# Motors_and_Steering.net
KiCad netlist of a schematic drawn in Altium Designer
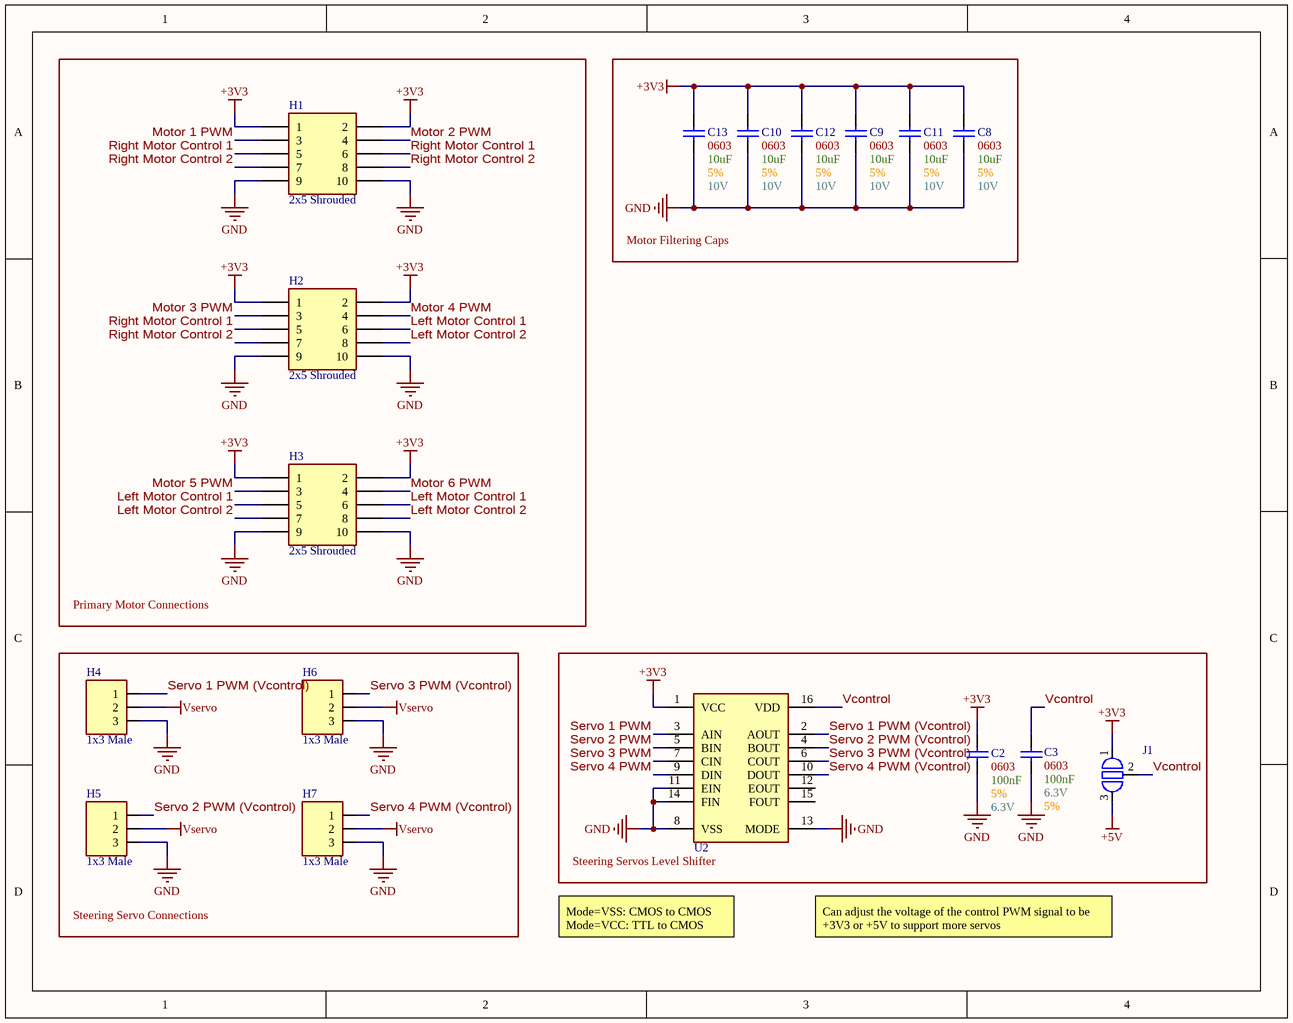
[diagram p0: Motors and Steering.SchDoc]

(export (version "E")
  (design (tool "Eeschema 10.0.6"))
  (components
    (comp (ref "C2")
      (value "[Cap] SMD Nonpolarized")
      (footprint "[Cap] SMD 0603")
      (fields
        (field (name "SIZE PACKAGE") "0603")
        (field (name "CAPACITANCE") "100nF")
        (field (name "VOLTAGE") "6.3V")
        (field (name "TOLERANCE") "5%")
      )
      (libsource (lib "RADM Components") (part "[Cap] SMD Nonpolarized"))
    )
    (comp (ref "C3")
      (value "[Cap] SMD Nonpolarized")
      (footprint "[Cap] SMD 0603")
      (fields
        (field (name "SIZE PACKAGE") "0603")
        (field (name "CAPACITANCE") "100nF")
        (field (name "VOLTAGE") "6.3V")
        (field (name "TOLERANCE") "5%")
      )
      (libsource (lib "RADM Components") (part "[Cap] SMD Nonpolarized"))
    )
    (comp (ref "C8")
      (value "[Cap] SMD Nonpolarized")
      (footprint "[Cap] SMD 0603")
      (fields
        (field (name "SIZE PACKAGE") "0603")
        (field (name "CAPACITANCE") "10uF")
        (field (name "VOLTAGE") "10V")
        (field (name "TOLERANCE") "5%")
      )
      (libsource (lib "RADM Components") (part "[Cap] SMD Nonpolarized"))
    )
    (comp (ref "C9")
      (value "[Cap] SMD Nonpolarized")
      (footprint "[Cap] SMD 0603")
      (fields
        (field (name "SIZE PACKAGE") "0603")
        (field (name "CAPACITANCE") "10uF")
        (field (name "VOLTAGE") "10V")
        (field (name "TOLERANCE") "5%")
      )
      (libsource (lib "RADM Components") (part "[Cap] SMD Nonpolarized"))
    )
    (comp (ref "C10")
      (value "[Cap] SMD Nonpolarized")
      (footprint "[Cap] SMD 0603")
      (fields
        (field (name "SIZE PACKAGE") "0603")
        (field (name "CAPACITANCE") "10uF")
        (field (name "VOLTAGE") "10V")
        (field (name "TOLERANCE") "5%")
      )
      (libsource (lib "RADM Components") (part "[Cap] SMD Nonpolarized"))
    )
    (comp (ref "C11")
      (value "[Cap] SMD Nonpolarized")
      (footprint "[Cap] SMD 0603")
      (fields
        (field (name "SIZE PACKAGE") "0603")
        (field (name "CAPACITANCE") "10uF")
        (field (name "VOLTAGE") "10V")
        (field (name "TOLERANCE") "5%")
      )
      (libsource (lib "RADM Components") (part "[Cap] SMD Nonpolarized"))
    )
    (comp (ref "C12")
      (value "[Cap] SMD Nonpolarized")
      (footprint "[Cap] SMD 0603")
      (fields
        (field (name "SIZE PACKAGE") "0603")
        (field (name "CAPACITANCE") "10uF")
        (field (name "VOLTAGE") "10V")
        (field (name "TOLERANCE") "5%")
      )
      (libsource (lib "RADM Components") (part "[Cap] SMD Nonpolarized"))
    )
    (comp (ref "C13")
      (value "[Cap] SMD Nonpolarized")
      (footprint "[Cap] SMD 0603")
      (fields
        (field (name "SIZE PACKAGE") "0603")
        (field (name "CAPACITANCE") "10uF")
        (field (name "VOLTAGE") "10V")
        (field (name "TOLERANCE") "5%")
      )
      (libsource (lib "RADM Components") (part "[Cap] SMD Nonpolarized"))
    )
    (comp (ref "H1")
      (value "2x5 Shrouded")
      (footprint "[Header] Shrouded 2x5 Male")
      (description "BHR-10-VUA")
      (libsource (lib "RADM Connectors") (part "[Header] Shrouded 2x5 Male"))
    )
    (comp (ref "H2")
      (value "2x5 Shrouded")
      (footprint "[Header] Shrouded 2x5 Male")
      (description "BHR-10-VUA")
      (libsource (lib "RADM Connectors") (part "[Header] Shrouded 2x5 Male"))
    )
    (comp (ref "H3")
      (value "2x5 Shrouded")
      (footprint "[Header] Shrouded 2x5 Male")
      (description "BHR-10-VUA")
      (libsource (lib "RADM Connectors") (part "[Header] Shrouded 2x5 Male"))
    )
    (comp (ref "H4")
      (value "1x3 Male")
      (footprint "[Header] Shrouded 1x3 Male")
      (description "070543-0037\r\nMates with 005057-9403")
      (libsource (lib "RADM Connectors") (part "[Header] Shrouded 1x3 Male"))
    )
    (comp (ref "H5")
      (value "1x3 Male")
      (footprint "[Header] Shrouded 1x3 Male")
      (description "070543-0037\r\nMates with 005057-9403")
      (libsource (lib "RADM Connectors") (part "[Header] Shrouded 1x3 Male"))
    )
    (comp (ref "H6")
      (value "1x3 Male")
      (footprint "[Header] Shrouded 1x3 Male")
      (description "070543-0037\r\nMates with 005057-9403")
      (libsource (lib "RADM Connectors") (part "[Header] Shrouded 1x3 Male"))
    )
    (comp (ref "H7")
      (value "1x3 Male")
      (footprint "[Header] Shrouded 1x3 Male")
      (description "070543-0037\r\nMates with 005057-9403")
      (libsource (lib "RADM Connectors") (part "[Header] Shrouded 1x3 Male"))
    )
    (comp (ref "J1")
      (value "Thru-Hole Jumper")
      (footprint "[Jumper] Thru-Hole 3pin")
      (description "Clip Jumper")
      (libsource (lib "RADM Components") (part "[Jump] Thru-Hole 3pin"))
    )
    (comp (ref "U2")
      (value "[IC] Level Shifter Unidirectional 3-18V")
      (footprint "[IC] Level Shifter Unidirectional 3-18V")
      (description "MC14504BDTR2G")
      (libsource (lib "RADM Components") (part "[IC] Level Shifter Unidirectional 3-18V"))
    )
  )
  (nets
    (net (code "1") (name "+3V3") (class "Default")
      (node (ref "C10") (pin "2") (pinfunction "2_2") (pintype "passive"))
      (node (ref "C11") (pin "2") (pinfunction "2_2") (pintype "passive"))
      (node (ref "C12") (pin "2") (pinfunction "2_2") (pintype "passive"))
      (node (ref "C13") (pin "2") (pinfunction "2_2") (pintype "passive"))
      (node (ref "C2") (pin "2") (pinfunction "2_2") (pintype "passive"))
      (node (ref "C8") (pin "2") (pinfunction "2_2") (pintype "passive"))
      (node (ref "C9") (pin "2") (pinfunction "2_2") (pintype "passive"))
      (node (ref "H1") (pin "1") (pinfunction "1_1") (pintype "passive"))
      (node (ref "H1") (pin "2") (pinfunction "2_2") (pintype "passive"))
      (node (ref "H2") (pin "1") (pinfunction "1_1") (pintype "passive"))
      (node (ref "H2") (pin "2") (pinfunction "2_2") (pintype "passive"))
      (node (ref "H3") (pin "1") (pinfunction "1_1") (pintype "passive"))
      (node (ref "H3") (pin "2") (pinfunction "2_2") (pintype "passive"))
      (node (ref "J1") (pin "1") (pintype "passive"))
      (node (ref "U2") (pin "1") (pinfunction "VCC_1") (pintype "passive"))
    )
    (net (code "2") (name "+5V") (class "Default") (node (ref "J1") (pin "3") (pintype "passive")))
    (net (code "3") (name "/Left Motor Control 1") (class "Default")
      (node (ref "H2") (pin "6") (pinfunction "6_6") (pintype "passive"))
      (node (ref "H3") (pin "5") (pinfunction "5_5") (pintype "passive"))
      (node (ref "H3") (pin "6") (pinfunction "6_6") (pintype "passive"))
    )
    (net (code "4") (name "/Left Motor Control 2") (class "Default")
      (node (ref "H2") (pin "8") (pinfunction "8_8") (pintype "passive"))
      (node (ref "H3") (pin "7") (pinfunction "7_7") (pintype "passive"))
      (node (ref "H3") (pin "8") (pinfunction "8_8") (pintype "passive"))
    )
    (net (code "5") (name "/Motor 1 PWM") (class "Default")
      (node (ref "H1") (pin "3") (pinfunction "3_3") (pintype "passive"))
    )
    (net (code "6") (name "/Motor 2 PWM") (class "Default")
      (node (ref "H1") (pin "4") (pinfunction "4_4") (pintype "passive"))
    )
    (net (code "7") (name "/Motor 3 PWM") (class "Default")
      (node (ref "H2") (pin "3") (pinfunction "3_3") (pintype "passive"))
    )
    (net (code "8") (name "/Motor 4 PWM") (class "Default")
      (node (ref "H2") (pin "4") (pinfunction "4_4") (pintype "passive"))
    )
    (net (code "9") (name "/Motor 5 PWM") (class "Default")
      (node (ref "H3") (pin "3") (pinfunction "3_3") (pintype "passive"))
    )
    (net (code "10") (name "/Motor 6 PWM") (class "Default")
      (node (ref "H3") (pin "4") (pinfunction "4_4") (pintype "passive"))
    )
    (net (code "11") (name "/Right Motor Control 1") (class "Default")
      (node (ref "H1") (pin "5") (pinfunction "5_5") (pintype "passive"))
      (node (ref "H1") (pin "6") (pinfunction "6_6") (pintype "passive"))
      (node (ref "H2") (pin "5") (pinfunction "5_5") (pintype "passive"))
    )
    (net (code "12") (name "/Right Motor Control 2") (class "Default")
      (node (ref "H1") (pin "7") (pinfunction "7_7") (pintype "passive"))
      (node (ref "H1") (pin "8") (pinfunction "8_8") (pintype "passive"))
      (node (ref "H2") (pin "7") (pinfunction "7_7") (pintype "passive"))
    )
    (net (code "13") (name "/Servo 1 PWM") (class "Default")
      (node (ref "U2") (pin "3") (pinfunction "AIN_3") (pintype "passive"))
    )
    (net (code "14") (name "/Servo 1 PWM (Vcontrol)") (class "Default")
      (node (ref "H4") (pin "1") (pinfunction "1_1") (pintype "passive"))
      (node (ref "U2") (pin "2") (pinfunction "AOUT_2") (pintype "passive"))
    )
    (net (code "15") (name "/Servo 2 PWM") (class "Default")
      (node (ref "U2") (pin "5") (pinfunction "BIN_5") (pintype "passive"))
    )
    (net (code "16") (name "/Servo 2 PWM (Vcontrol)") (class "Default")
      (node (ref "H5") (pin "1") (pinfunction "1_1") (pintype "passive"))
      (node (ref "U2") (pin "4") (pinfunction "BOUT_4") (pintype "passive"))
    )
    (net (code "17") (name "/Servo 3 PWM") (class "Default")
      (node (ref "U2") (pin "7") (pinfunction "CIN_7") (pintype "passive"))
    )
    (net (code "18") (name "/Servo 3 PWM (Vcontrol)") (class "Default")
      (node (ref "H6") (pin "1") (pinfunction "1_1") (pintype "passive"))
      (node (ref "U2") (pin "6") (pinfunction "COUT_6") (pintype "passive"))
    )
    (net (code "19") (name "/Servo 4 PWM") (class "Default")
      (node (ref "U2") (pin "9") (pinfunction "DIN_9") (pintype "passive"))
    )
    (net (code "20") (name "/Servo 4 PWM (Vcontrol)") (class "Default")
      (node (ref "H7") (pin "1") (pinfunction "1_1") (pintype "passive"))
      (node (ref "U2") (pin "10") (pinfunction "DOUT_10") (pintype "passive"))
    )
    (net (code "21") (name "/Vcontrol") (class "Default")
      (node (ref "C3") (pin "1") (pinfunction "1_1") (pintype "passive"))
      (node (ref "J1") (pin "2") (pinfunction "Common_2") (pintype "power_in"))
      (node (ref "U2") (pin "16") (pinfunction "VDD_16") (pintype "passive"))
    )
    (net (code "22") (name "GND") (class "Default")
      (node (ref "C10") (pin "1") (pinfunction "1_1") (pintype "passive"))
      (node (ref "C11") (pin "1") (pinfunction "1_1") (pintype "passive"))
      (node (ref "C12") (pin "1") (pinfunction "1_1") (pintype "passive"))
      (node (ref "C13") (pin "1") (pinfunction "1_1") (pintype "passive"))
      (node (ref "C2") (pin "1") (pinfunction "1_1") (pintype "passive"))
      (node (ref "C3") (pin "2") (pinfunction "2_2") (pintype "passive"))
      (node (ref "C8") (pin "1") (pinfunction "1_1") (pintype "passive"))
      (node (ref "C9") (pin "1") (pinfunction "1_1") (pintype "passive"))
      (node (ref "H1") (pin "10") (pinfunction "10_10") (pintype "passive"))
      (node (ref "H1") (pin "9") (pinfunction "9_9") (pintype "passive"))
      (node (ref "H2") (pin "10") (pinfunction "10_10") (pintype "passive"))
      (node (ref "H2") (pin "9") (pinfunction "9_9") (pintype "passive"))
      (node (ref "H3") (pin "10") (pinfunction "10_10") (pintype "passive"))
      (node (ref "H3") (pin "9") (pinfunction "9_9") (pintype "passive"))
      (node (ref "H4") (pin "3") (pinfunction "3_3") (pintype "passive"))
      (node (ref "H5") (pin "3") (pinfunction "3_3") (pintype "passive"))
      (node (ref "H6") (pin "3") (pinfunction "3_3") (pintype "passive"))
      (node (ref "H7") (pin "3") (pinfunction "3_3") (pintype "passive"))
      (node (ref "U2") (pin "11") (pinfunction "EIN_11") (pintype "passive"))
      (node (ref "U2") (pin "13") (pinfunction "MODE_13") (pintype "passive"))
      (node (ref "U2") (pin "14") (pinfunction "FIN_14") (pintype "passive"))
      (node (ref "U2") (pin "8") (pinfunction "VSS_8") (pintype "passive"))
    )
    (net (code "23") (name "Vservo") (class "Default")
      (node (ref "H4") (pin "2") (pinfunction "2_2") (pintype "passive"))
      (node (ref "H5") (pin "2") (pinfunction "2_2") (pintype "passive"))
      (node (ref "H6") (pin "2") (pinfunction "2_2") (pintype "passive"))
      (node (ref "H7") (pin "2") (pinfunction "2_2") (pintype "passive"))
    )
    (net (code "24") (name "unconnected-(U2-EOUT-Pad12)") (class "Default")
      (node (ref "U2") (pin "12") (pinfunction "EOUT_12") (pintype "passive"))
    )
    (net (code "25") (name "unconnected-(U2-FOUT-Pad15)") (class "Default")
      (node (ref "U2") (pin "15") (pinfunction "FOUT_15") (pintype "passive"))
    )
  )
)
